# PSU_NCP630_ADJ.net
KiCad netlist of a schematic drawn in Altium Designer
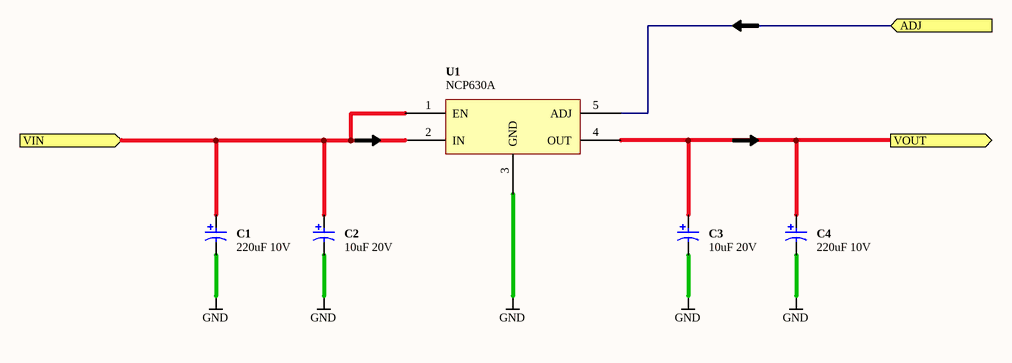
[diagram p0: PSU_NCP630_ADJ.SchDoc]

(export (version "E")
  (design (tool "Eeschema 10.0.6"))
  (components
    (comp (ref "C1")
      (value "220uF 10V")
      (footprint "CAPC7343-STAR")
      (description "Capacitor, Tantalum, 220uF 10% 10V MCCT-D (7343-31)")
      (fields (field (name "TOLERANCE") "10 %"))
      (libsource (lib "altium-import") (part "root_0_CAP-P_"))
    )
    (comp (ref "C2")
      (value "10uF 20V")
      (footprint "CAPC3528-STAR")
      (description "Capacitor, Tantalum, 10uF 10% 20V MCCT-B (3528)")
      (fields (field (name "TOLERANCE") "10 %"))
      (libsource (lib "altium-import") (part "root_0_CAP-P_"))
    )
    (comp (ref "C3")
      (value "10uF 20V")
      (footprint "CAPC3528-STAR")
      (description "Capacitor, Tantalum, 10uF 10% 20V MCCT-B (3528)")
      (fields (field (name "TOLERANCE") "10 %"))
      (libsource (lib "altium-import") (part "root_0_CAP-P_"))
    )
    (comp (ref "C4")
      (value "220uF 10V")
      (footprint "CAPC7343-STAR")
      (description "Capacitor, Tantalum, 220uF 10% 10V MCCT-D (7343-31)")
      (fields (field (name "TOLERANCE") "10 %"))
      (libsource (lib "altium-import") (part "root_0_CAP-P_"))
    )
    (comp (ref "U1")
      (value "NCP630A")
      (footprint "TO-263-2")
      (description "NCP630A, 3.0A Fast Linear Voltage Regulator, D2PAK")
      (libsource (lib "AltiumDesignLibrary") (part "NCP630A"))
    )
  )
  (nets
    (net (code "1") (name "/ADJ") (class "Default")
      (node (ref "U1") (pin "5") (pinfunction "ADJ_5") (pintype "passive"))
    )
    (net (code "2") (name "/VIN") (class "Default")
      (node (ref "C1") (pin "1") (pinfunction "1_1") (pintype "passive"))
      (node (ref "C2") (pin "1") (pinfunction "1_1") (pintype "passive"))
      (node (ref "U1") (pin "1") (pinfunction "EN_1") (pintype "passive"))
      (node (ref "U1") (pin "2") (pinfunction "IN_2") (pintype "passive"))
    )
    (net (code "3") (name "/VOUT") (class "Default")
      (node (ref "C3") (pin "1") (pinfunction "1_1") (pintype "passive"))
      (node (ref "C4") (pin "1") (pinfunction "1_1") (pintype "passive"))
      (node (ref "U1") (pin "4") (pinfunction "OUT_4") (pintype "passive"))
    )
    (net (code "4") (name "GND") (class "Default")
      (node (ref "C1") (pin "2") (pinfunction "2_2") (pintype "passive"))
      (node (ref "C2") (pin "2") (pinfunction "2_2") (pintype "passive"))
      (node (ref "C3") (pin "2") (pinfunction "2_2") (pintype "passive"))
      (node (ref "C4") (pin "2") (pinfunction "2_2") (pintype "passive"))
      (node (ref "U1") (pin "3") (pinfunction "GND_3") (pintype "passive"))
    )
  )
)
